# RF-CON-NFC.net
KiCad netlist of a schematic drawn in Altium Designer
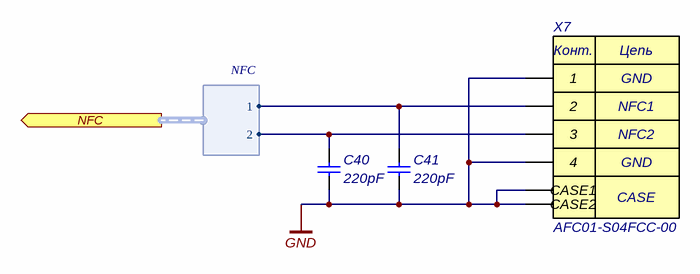
[diagram p0: RF-CON-NFC.SchDoc]

(export (version "E")
  (design (tool "Eeschema 10.0.6"))
  (components
    (comp (ref "C40")
      (value "220pF")
      (footprint "C0402")
      (fields
        (field (name "PART NUMBER") "0402-NP0-50V-220pF±5%")
        (field (name "VOLTAGE") "50V")
        (field (name "TOLERANCE") "5%")
      )
      (libsource (lib "ATB") (part "C"))
    )
    (comp (ref "C41")
      (value "220pF")
      (footprint "C0402")
      (fields
        (field (name "PART NUMBER") "0402-NP0-50V-220pF±5%")
        (field (name "VOLTAGE") "50V")
        (field (name "TOLERANCE") "5%")
      )
      (libsource (lib "ATB") (part "C"))
    )
    (comp (ref "X7")
      (value "AFC01-S04FCC-00")
      (footprint "505110-0492")
      (description "Clamshell 4P Bottom Contact Surface Mount, Right Angle 0.5mm, FFC/FPC Connector")
      (fields (field (name "MANUFACTURER") "JUSHUO"))
      (libsource (lib "ATB") (part "H4+2xCase"))
    )
  )
  (nets
    (net (code "3") (name "GND") (class "Default")
      (node (ref "C40") (pin "2") (pinfunction "2_2") (pintype "passive"))
      (node (ref "C41") (pin "2") (pinfunction "2_2") (pintype "passive"))
      (node (ref "X7") (pin "1") (pinfunction "1_1") (pintype "passive"))
      (node (ref "X7") (pin "4") (pinfunction "4_4") (pintype "passive"))
      (node (ref "X7") (pin "CASE1") (pinfunction "CASE1_CASE1") (pintype "passive"))
      (node (ref "X7") (pin "CASE2") (pinfunction "CASE2_CASE2") (pintype "passive"))
    )
    (net (code "4") (name "Net-(C40-Pad1)") (class "Default")
      (node (ref "C40") (pin "1") (pinfunction "1_1") (pintype "passive"))
      (node (ref "X7") (pin "3") (pinfunction "3_3") (pintype "passive"))
    )
    (net (code "5") (name "Net-(C41-Pad1)") (class "Default")
      (node (ref "C41") (pin "1") (pinfunction "1_1") (pintype "passive"))
      (node (ref "X7") (pin "2") (pinfunction "2_2") (pintype "passive"))
    )
  )
)
